# cdf-modular-bridge-rev4.net
KiCad netlist of a schematic drawn in EAGLE
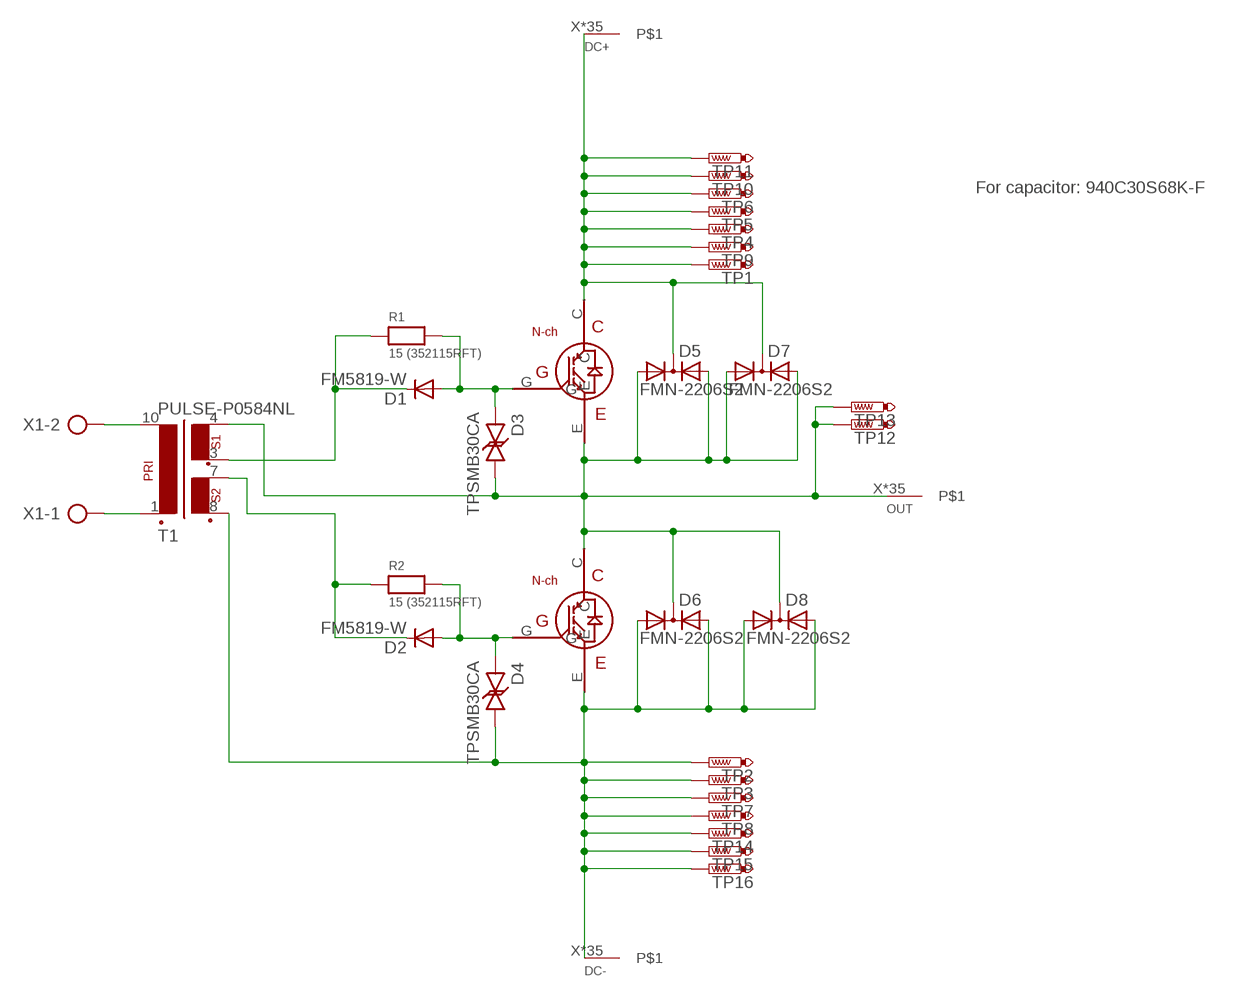
[diagram p0: schematic, sheet 1]

(export (version "E")
  (design (tool "Eeschema 10.0.6"))
  (components
    (comp (ref "D1")
      (value "FM5819-W")
      (footprint "eagle-import:DO214AC")
      (fields (field (name "MF") "Fairchild") (field (name "MPN") "S1A"))
      (libsource (lib "eagle-import") (part "S1A"))
    )
    (comp (ref "D2")
      (value "FM5819-W")
      (footprint "eagle-import:DO214AC")
      (fields (field (name "MF") "Fairchild") (field (name "MPN") "S1A"))
      (libsource (lib "eagle-import") (part "S1A"))
    )
    (comp (ref "D3")
      (value "TPSMB30CA")
      (footprint "eagle-import:TPSMB15CA")
      (libsource (lib "eagle-import") (part "TPSMB15CA"))
    )
    (comp (ref "D4")
      (value "TPSMB30CA")
      (footprint "eagle-import:TPSMB15CA")
      (libsource (lib "eagle-import") (part "TPSMB15CA"))
    )
    (comp (ref "D5")
      (value "FMN-2206S2")
      (footprint "eagle-import:TO220-CDF-SPACED-LEGS")
      (libsource (lib "eagle-import") (part "FMN-2206S2"))
    )
    (comp (ref "D6")
      (value "FMN-2206S2")
      (footprint "eagle-import:TO220-CDF-SPACED-LEGS")
      (libsource (lib "eagle-import") (part "FMN-2206S2"))
    )
    (comp (ref "D7")
      (value "FMN-2206S2")
      (footprint "eagle-import:TO220-CDF-SPACED-LEGS")
      (libsource (lib "eagle-import") (part "FMN-2206S2"))
    )
    (comp (ref "D8")
      (value "FMN-2206S2")
      (footprint "eagle-import:TO220-CDF-SPACED-LEGS")
      (libsource (lib "eagle-import") (part "FMN-2206S2"))
    )
    (comp (ref "DC+")
      (value "BIG-ASS-HOLE")
      (footprint "eagle-import:BIG-ASS-HOLE")
      (libsource (lib "eagle-import") (part "BIG-ASS-HOLE"))
    )
    (comp (ref "DC-")
      (value "BIG-ASS-HOLE")
      (footprint "eagle-import:BIG-ASS-HOLE")
      (libsource (lib "eagle-import") (part "BIG-ASS-HOLE"))
    )
    (comp (ref "OUT")
      (value "BIG-ASS-HOLE")
      (footprint "eagle-import:BIG-ASS-HOLE")
      (libsource (lib "eagle-import") (part "BIG-ASS-HOLE"))
    )
    (comp (ref "Q1")
      (value "Ixgh48n60a3")
      (footprint "eagle-import:IXGH40N60A")
      (libsource (lib "eagle-import") (part "IXGH40N60A"))
    )
    (comp (ref "Q2")
      (value "Ixgh48n60a3")
      (footprint "eagle-import:IXGH40N60A")
      (libsource (lib "eagle-import") (part "IXGH40N60A"))
    )
    (comp (ref "R1")
      (value "15 (352115RFT)")
      (footprint "eagle-import:2512")
      (libsource (lib "eagle-import") (part "RESISTOR2512"))
    )
    (comp (ref "R2")
      (value "15 (352115RFT)")
      (footprint "eagle-import:2512")
      (libsource (lib "eagle-import") (part "RESISTOR2512"))
    )
    (comp (ref "T1")
      (value "PULSE-P0584NL")
      (footprint "eagle-import:PULSE-P0584NL")
      (libsource (lib "eagle-import") (part "PULSE-P0584NL"))
    )
    (comp (ref "TP1")
      (value "PTR1PAD1-17")
      (footprint "eagle-import:P1-17")
      (libsource (lib "eagle-import") (part "PTR1PAD1-17"))
    )
    (comp (ref "TP2")
      (value "PTR1PAD1-17")
      (footprint "eagle-import:P1-17")
      (libsource (lib "eagle-import") (part "PTR1PAD1-17"))
    )
    (comp (ref "TP3")
      (value "PTR1PAD1-17")
      (footprint "eagle-import:P1-17")
      (libsource (lib "eagle-import") (part "PTR1PAD1-17"))
    )
    (comp (ref "TP4")
      (value "PTR1PAD1-17")
      (footprint "eagle-import:P1-17")
      (libsource (lib "eagle-import") (part "PTR1PAD1-17"))
    )
    (comp (ref "TP5")
      (value "PTR1PAD1-17")
      (footprint "eagle-import:P1-17")
      (libsource (lib "eagle-import") (part "PTR1PAD1-17"))
    )
    (comp (ref "TP6")
      (value "PTR1PAD1-17")
      (footprint "eagle-import:P1-17")
      (libsource (lib "eagle-import") (part "PTR1PAD1-17"))
    )
    (comp (ref "TP7")
      (value "PTR1PAD1-17")
      (footprint "eagle-import:P1-17")
      (libsource (lib "eagle-import") (part "PTR1PAD1-17"))
    )
    (comp (ref "TP8")
      (value "PTR1PAD1-17")
      (footprint "eagle-import:P1-17")
      (libsource (lib "eagle-import") (part "PTR1PAD1-17"))
    )
    (comp (ref "TP9")
      (value "PTR1PAD1-17")
      (footprint "eagle-import:P1-17")
      (libsource (lib "eagle-import") (part "PTR1PAD1-17"))
    )
    (comp (ref "TP10")
      (value "PTR1PAD1-17")
      (footprint "eagle-import:P1-17")
      (libsource (lib "eagle-import") (part "PTR1PAD1-17"))
    )
    (comp (ref "TP11")
      (value "PTR1PAD1-17")
      (footprint "eagle-import:P1-17")
      (libsource (lib "eagle-import") (part "PTR1PAD1-17"))
    )
    (comp (ref "TP12")
      (value "PTR1PAD1-17")
      (footprint "eagle-import:P1-17")
      (libsource (lib "eagle-import") (part "PTR1PAD1-17"))
    )
    (comp (ref "TP13")
      (value "PTR1PAD1-17")
      (footprint "eagle-import:P1-17")
      (libsource (lib "eagle-import") (part "PTR1PAD1-17"))
    )
    (comp (ref "TP14")
      (value "PTR1PAD1-17")
      (footprint "eagle-import:P1-17")
      (libsource (lib "eagle-import") (part "PTR1PAD1-17"))
    )
    (comp (ref "TP15")
      (value "PTR1PAD1-17")
      (footprint "eagle-import:P1-17")
      (libsource (lib "eagle-import") (part "PTR1PAD1-17"))
    )
    (comp (ref "TP16")
      (value "PTR1PAD1-17")
      (footprint "eagle-import:P1-17")
      (libsource (lib "eagle-import") (part "PTR1PAD1-17"))
    )
    (comp (ref "X1")
      (value "AK500/2")
      (footprint "eagle-import:AK500_2")
      (libsource (lib "eagle-import") (part "AK500/2"))
    )
  )
  (nets
    (net (code "1") (name "Net-(D1-PadA)") (class "Default")
      (node (ref "D1") (pin "A") (pinfunction "A_A") (pintype "passive"))
      (node (ref "D3") (pin "P$1") (pinfunction "P$1_P$1") (pintype "passive"))
      (node (ref "Q1") (pin "G") (pinfunction "G_G") (pintype "bidirectional"))
      (node (ref "R1") (pin "2") (pinfunction "2_2") (pintype "passive"))
    )
    (net (code "2") (name "Net-(D2-PadA)") (class "Default")
      (node (ref "D2") (pin "A") (pinfunction "A_A") (pintype "passive"))
      (node (ref "D4") (pin "P$1") (pinfunction "P$1_P$1") (pintype "passive"))
      (node (ref "Q2") (pin "G") (pinfunction "G_G") (pintype "bidirectional"))
      (node (ref "R2") (pin "2") (pinfunction "2_2") (pintype "passive"))
    )
    (net (code "3") (name "Net-(D5-PadC)") (class "Default")
      (node (ref "D5") (pin "C") (pinfunction "C_C") (pintype "passive"))
      (node (ref "D7") (pin "C") (pinfunction "C_C") (pintype "passive"))
      (node (ref "DC+") (pin "X") (pinfunction "P$1_X") (pintype "bidirectional"))
      (node (ref "DC+") (pin "X@1") (pinfunction "P$1_X@1") (pintype "bidirectional"))
      (node (ref "DC+") (pin "X@10") (pinfunction "P$1_X@10") (pintype "bidirectional"))
      (node (ref "DC+") (pin "X@11") (pinfunction "P$1_X@11") (pintype "bidirectional"))
      (node (ref "DC+") (pin "X@12") (pinfunction "P$1_X@12") (pintype "bidirectional"))
      (node (ref "DC+") (pin "X@120") (pinfunction "P$1_X@120") (pintype "bidirectional"))
      (node (ref "DC+") (pin "X@13") (pinfunction "P$1_X@13") (pintype "bidirectional"))
      (node (ref "DC+") (pin "X@14") (pinfunction "P$1_X@14") (pintype "bidirectional"))
      (node (ref "DC+") (pin "X@15") (pinfunction "P$1_X@15") (pintype "bidirectional"))
      (node (ref "DC+") (pin "X@16") (pinfunction "P$1_X@16") (pintype "bidirectional"))
      (node (ref "DC+") (pin "X@17") (pinfunction "P$1_X@17") (pintype "bidirectional"))
      (node (ref "DC+") (pin "X@18") (pinfunction "P$1_X@18") (pintype "bidirectional"))
      (node (ref "DC+") (pin "X@19") (pinfunction "P$1_X@19") (pintype "bidirectional"))
      (node (ref "DC+") (pin "X@2") (pinfunction "P$1_X@2") (pintype "bidirectional"))
      (node (ref "DC+") (pin "X@20") (pinfunction "P$1_X@20") (pintype "bidirectional"))
      (node (ref "DC+") (pin "X@21") (pinfunction "P$1_X@21") (pintype "bidirectional"))
      (node (ref "DC+") (pin "X@22") (pinfunction "P$1_X@22") (pintype "bidirectional"))
      (node (ref "DC+") (pin "X@23") (pinfunction "P$1_X@23") (pintype "bidirectional"))
      (node (ref "DC+") (pin "X@24") (pinfunction "P$1_X@24") (pintype "bidirectional"))
      (node (ref "DC+") (pin "X@25") (pinfunction "P$1_X@25") (pintype "bidirectional"))
      (node (ref "DC+") (pin "X@26") (pinfunction "P$1_X@26") (pintype "bidirectional"))
      (node (ref "DC+") (pin "X@27") (pinfunction "P$1_X@27") (pintype "bidirectional"))
      (node (ref "DC+") (pin "X@28") (pinfunction "P$1_X@28") (pintype "bidirectional"))
      (node (ref "DC+") (pin "X@29") (pinfunction "P$1_X@29") (pintype "bidirectional"))
      (node (ref "DC+") (pin "X@3") (pinfunction "P$1_X@3") (pintype "bidirectional"))
      (node (ref "DC+") (pin "X@30") (pinfunction "P$1_X@30") (pintype "bidirectional"))
      (node (ref "DC+") (pin "X@31") (pinfunction "P$1_X@31") (pintype "bidirectional"))
      (node (ref "DC+") (pin "X@32") (pinfunction "P$1_X@32") (pintype "bidirectional"))
      (node (ref "DC+") (pin "X@34") (pinfunction "P$1_X@34") (pintype "bidirectional"))
      (node (ref "DC+") (pin "X@4") (pinfunction "P$1_X@4") (pintype "bidirectional"))
      (node (ref "DC+") (pin "X@5") (pinfunction "P$1_X@5") (pintype "bidirectional"))
      (node (ref "DC+") (pin "X@6") (pinfunction "P$1_X@6") (pintype "bidirectional"))
      (node (ref "DC+") (pin "X@7") (pinfunction "P$1_X@7") (pintype "bidirectional"))
      (node (ref "DC+") (pin "X@8") (pinfunction "P$1_X@8") (pintype "bidirectional"))
      (node (ref "DC+") (pin "X@9") (pinfunction "P$1_X@9") (pintype "bidirectional"))
      (node (ref "Q1") (pin "C") (pinfunction "C_C") (pintype "bidirectional"))
      (node (ref "TP1") (pin "TP") (pinfunction "TP_TP") (pintype "input"))
      (node (ref "TP10") (pin "TP") (pinfunction "TP_TP") (pintype "input"))
      (node (ref "TP11") (pin "TP") (pinfunction "TP_TP") (pintype "input"))
      (node (ref "TP4") (pin "TP") (pinfunction "TP_TP") (pintype "input"))
      (node (ref "TP5") (pin "TP") (pinfunction "TP_TP") (pintype "input"))
      (node (ref "TP6") (pin "TP") (pinfunction "TP_TP") (pintype "input"))
      (node (ref "TP9") (pin "TP") (pinfunction "TP_TP") (pintype "input"))
    )
    (net (code "4") (name "Net-(T1-PRI_NEG)") (class "Default")
      (node (ref "T1") (pin "10") (pinfunction "PRI_NEG_10") (pintype "passive"))
      (node (ref "X1") (pin "2") (pinfunction "KL_2") (pintype "passive"))
    )
    (net (code "5") (name "Net-(T1-PRI_POS)") (class "Default")
      (node (ref "T1") (pin "1") (pinfunction "PRI_POS_1") (pintype "passive"))
      (node (ref "X1") (pin "1") (pinfunction "KL_1") (pintype "passive"))
    )
    (net (code "6") (name "Net-(T1-SEC1_NEG)") (class "Default")
      (node (ref "D3") (pin "P$2") (pinfunction "P$2_P$2") (pintype "passive"))
      (node (ref "D5") (pin "A1") (pinfunction "A1_A1") (pintype "passive"))
      (node (ref "D5") (pin "A2") (pinfunction "A2_A2") (pintype "passive"))
      (node (ref "D6") (pin "C") (pinfunction "C_C") (pintype "passive"))
      (node (ref "D7") (pin "A1") (pinfunction "A1_A1") (pintype "passive"))
      (node (ref "D7") (pin "A2") (pinfunction "A2_A2") (pintype "passive"))
      (node (ref "D8") (pin "C") (pinfunction "C_C") (pintype "passive"))
      (node (ref "OUT") (pin "X") (pinfunction "P$1_X") (pintype "bidirectional"))
      (node (ref "OUT") (pin "X@1") (pinfunction "P$1_X@1") (pintype "bidirectional"))
      (node (ref "OUT") (pin "X@10") (pinfunction "P$1_X@10") (pintype "bidirectional"))
      (node (ref "OUT") (pin "X@11") (pinfunction "P$1_X@11") (pintype "bidirectional"))
      (node (ref "OUT") (pin "X@12") (pinfunction "P$1_X@12") (pintype "bidirectional"))
      (node (ref "OUT") (pin "X@120") (pinfunction "P$1_X@120") (pintype "bidirectional"))
      (node (ref "OUT") (pin "X@13") (pinfunction "P$1_X@13") (pintype "bidirectional"))
      (node (ref "OUT") (pin "X@14") (pinfunction "P$1_X@14") (pintype "bidirectional"))
      (node (ref "OUT") (pin "X@15") (pinfunction "P$1_X@15") (pintype "bidirectional"))
      (node (ref "OUT") (pin "X@16") (pinfunction "P$1_X@16") (pintype "bidirectional"))
      (node (ref "OUT") (pin "X@17") (pinfunction "P$1_X@17") (pintype "bidirectional"))
      (node (ref "OUT") (pin "X@18") (pinfunction "P$1_X@18") (pintype "bidirectional"))
      (node (ref "OUT") (pin "X@19") (pinfunction "P$1_X@19") (pintype "bidirectional"))
      (node (ref "OUT") (pin "X@2") (pinfunction "P$1_X@2") (pintype "bidirectional"))
      (node (ref "OUT") (pin "X@20") (pinfunction "P$1_X@20") (pintype "bidirectional"))
      (node (ref "OUT") (pin "X@21") (pinfunction "P$1_X@21") (pintype "bidirectional"))
      (node (ref "OUT") (pin "X@22") (pinfunction "P$1_X@22") (pintype "bidirectional"))
      (node (ref "OUT") (pin "X@23") (pinfunction "P$1_X@23") (pintype "bidirectional"))
      (node (ref "OUT") (pin "X@24") (pinfunction "P$1_X@24") (pintype "bidirectional"))
      (node (ref "OUT") (pin "X@25") (pinfunction "P$1_X@25") (pintype "bidirectional"))
      (node (ref "OUT") (pin "X@26") (pinfunction "P$1_X@26") (pintype "bidirectional"))
      (node (ref "OUT") (pin "X@27") (pinfunction "P$1_X@27") (pintype "bidirectional"))
      (node (ref "OUT") (pin "X@28") (pinfunction "P$1_X@28") (pintype "bidirectional"))
      (node (ref "OUT") (pin "X@29") (pinfunction "P$1_X@29") (pintype "bidirectional"))
      (node (ref "OUT") (pin "X@3") (pinfunction "P$1_X@3") (pintype "bidirectional"))
      (node (ref "OUT") (pin "X@30") (pinfunction "P$1_X@30") (pintype "bidirectional"))
      (node (ref "OUT") (pin "X@31") (pinfunction "P$1_X@31") (pintype "bidirectional"))
      (node (ref "OUT") (pin "X@32") (pinfunction "P$1_X@32") (pintype "bidirectional"))
      (node (ref "OUT") (pin "X@34") (pinfunction "P$1_X@34") (pintype "bidirectional"))
      (node (ref "OUT") (pin "X@4") (pinfunction "P$1_X@4") (pintype "bidirectional"))
      (node (ref "OUT") (pin "X@5") (pinfunction "P$1_X@5") (pintype "bidirectional"))
      (node (ref "OUT") (pin "X@6") (pinfunction "P$1_X@6") (pintype "bidirectional"))
      (node (ref "OUT") (pin "X@7") (pinfunction "P$1_X@7") (pintype "bidirectional"))
      (node (ref "OUT") (pin "X@8") (pinfunction "P$1_X@8") (pintype "bidirectional"))
      (node (ref "OUT") (pin "X@9") (pinfunction "P$1_X@9") (pintype "bidirectional"))
      (node (ref "Q1") (pin "E") (pinfunction "E_E") (pintype "bidirectional"))
      (node (ref "Q2") (pin "C") (pinfunction "C_C") (pintype "bidirectional"))
      (node (ref "T1") (pin "4") (pinfunction "SEC1_NEG_4") (pintype "passive"))
      (node (ref "TP12") (pin "TP") (pinfunction "TP_TP") (pintype "input"))
      (node (ref "TP13") (pin "TP") (pinfunction "TP_TP") (pintype "input"))
    )
    (net (code "7") (name "Net-(T1-SEC1_POS)") (class "Default")
      (node (ref "D1") (pin "C") (pinfunction "C_C") (pintype "passive"))
      (node (ref "R1") (pin "1") (pinfunction "1_1") (pintype "passive"))
      (node (ref "T1") (pin "3") (pinfunction "SEC1_POS_3") (pintype "passive"))
    )
    (net (code "8") (name "Net-(T1-SEC2_NEG)") (class "Default")
      (node (ref "D2") (pin "C") (pinfunction "C_C") (pintype "passive"))
      (node (ref "R2") (pin "1") (pinfunction "1_1") (pintype "passive"))
      (node (ref "T1") (pin "7") (pinfunction "SEC2_NEG_7") (pintype "passive"))
    )
    (net (code "9") (name "Net-(T1-SEC2_POS)") (class "Default")
      (node (ref "D4") (pin "P$2") (pinfunction "P$2_P$2") (pintype "passive"))
      (node (ref "D6") (pin "A1") (pinfunction "A1_A1") (pintype "passive"))
      (node (ref "D6") (pin "A2") (pinfunction "A2_A2") (pintype "passive"))
      (node (ref "D8") (pin "A1") (pinfunction "A1_A1") (pintype "passive"))
      (node (ref "D8") (pin "A2") (pinfunction "A2_A2") (pintype "passive"))
      (node (ref "DC-") (pin "X") (pinfunction "P$1_X") (pintype "bidirectional"))
      (node (ref "DC-") (pin "X@1") (pinfunction "P$1_X@1") (pintype "bidirectional"))
      (node (ref "DC-") (pin "X@10") (pinfunction "P$1_X@10") (pintype "bidirectional"))
      (node (ref "DC-") (pin "X@11") (pinfunction "P$1_X@11") (pintype "bidirectional"))
      (node (ref "DC-") (pin "X@12") (pinfunction "P$1_X@12") (pintype "bidirectional"))
      (node (ref "DC-") (pin "X@120") (pinfunction "P$1_X@120") (pintype "bidirectional"))
      (node (ref "DC-") (pin "X@13") (pinfunction "P$1_X@13") (pintype "bidirectional"))
      (node (ref "DC-") (pin "X@14") (pinfunction "P$1_X@14") (pintype "bidirectional"))
      (node (ref "DC-") (pin "X@15") (pinfunction "P$1_X@15") (pintype "bidirectional"))
      (node (ref "DC-") (pin "X@16") (pinfunction "P$1_X@16") (pintype "bidirectional"))
      (node (ref "DC-") (pin "X@17") (pinfunction "P$1_X@17") (pintype "bidirectional"))
      (node (ref "DC-") (pin "X@18") (pinfunction "P$1_X@18") (pintype "bidirectional"))
      (node (ref "DC-") (pin "X@19") (pinfunction "P$1_X@19") (pintype "bidirectional"))
      (node (ref "DC-") (pin "X@2") (pinfunction "P$1_X@2") (pintype "bidirectional"))
      (node (ref "DC-") (pin "X@20") (pinfunction "P$1_X@20") (pintype "bidirectional"))
      (node (ref "DC-") (pin "X@21") (pinfunction "P$1_X@21") (pintype "bidirectional"))
      (node (ref "DC-") (pin "X@22") (pinfunction "P$1_X@22") (pintype "bidirectional"))
      (node (ref "DC-") (pin "X@23") (pinfunction "P$1_X@23") (pintype "bidirectional"))
      (node (ref "DC-") (pin "X@24") (pinfunction "P$1_X@24") (pintype "bidirectional"))
      (node (ref "DC-") (pin "X@25") (pinfunction "P$1_X@25") (pintype "bidirectional"))
      (node (ref "DC-") (pin "X@26") (pinfunction "P$1_X@26") (pintype "bidirectional"))
      (node (ref "DC-") (pin "X@27") (pinfunction "P$1_X@27") (pintype "bidirectional"))
      (node (ref "DC-") (pin "X@28") (pinfunction "P$1_X@28") (pintype "bidirectional"))
      (node (ref "DC-") (pin "X@29") (pinfunction "P$1_X@29") (pintype "bidirectional"))
      (node (ref "DC-") (pin "X@3") (pinfunction "P$1_X@3") (pintype "bidirectional"))
      (node (ref "DC-") (pin "X@30") (pinfunction "P$1_X@30") (pintype "bidirectional"))
      (node (ref "DC-") (pin "X@31") (pinfunction "P$1_X@31") (pintype "bidirectional"))
      (node (ref "DC-") (pin "X@32") (pinfunction "P$1_X@32") (pintype "bidirectional"))
      (node (ref "DC-") (pin "X@34") (pinfunction "P$1_X@34") (pintype "bidirectional"))
      (node (ref "DC-") (pin "X@4") (pinfunction "P$1_X@4") (pintype "bidirectional"))
      (node (ref "DC-") (pin "X@5") (pinfunction "P$1_X@5") (pintype "bidirectional"))
      (node (ref "DC-") (pin "X@6") (pinfunction "P$1_X@6") (pintype "bidirectional"))
      (node (ref "DC-") (pin "X@7") (pinfunction "P$1_X@7") (pintype "bidirectional"))
      (node (ref "DC-") (pin "X@8") (pinfunction "P$1_X@8") (pintype "bidirectional"))
      (node (ref "DC-") (pin "X@9") (pinfunction "P$1_X@9") (pintype "bidirectional"))
      (node (ref "Q2") (pin "E") (pinfunction "E_E") (pintype "bidirectional"))
      (node (ref "T1") (pin "8") (pinfunction "SEC2_POS_8") (pintype "passive"))
      (node (ref "TP14") (pin "TP") (pinfunction "TP_TP") (pintype "input"))
      (node (ref "TP15") (pin "TP") (pinfunction "TP_TP") (pintype "input"))
      (node (ref "TP16") (pin "TP") (pinfunction "TP_TP") (pintype "input"))
      (node (ref "TP2") (pin "TP") (pinfunction "TP_TP") (pintype "input"))
      (node (ref "TP3") (pin "TP") (pinfunction "TP_TP") (pintype "input"))
      (node (ref "TP7") (pin "TP") (pinfunction "TP_TP") (pintype "input"))
      (node (ref "TP8") (pin "TP") (pinfunction "TP_TP") (pintype "input"))
    )
  )
)
